# PhaseShiftNetwork.net
KiCad netlist of a schematic drawn in Altium Designer
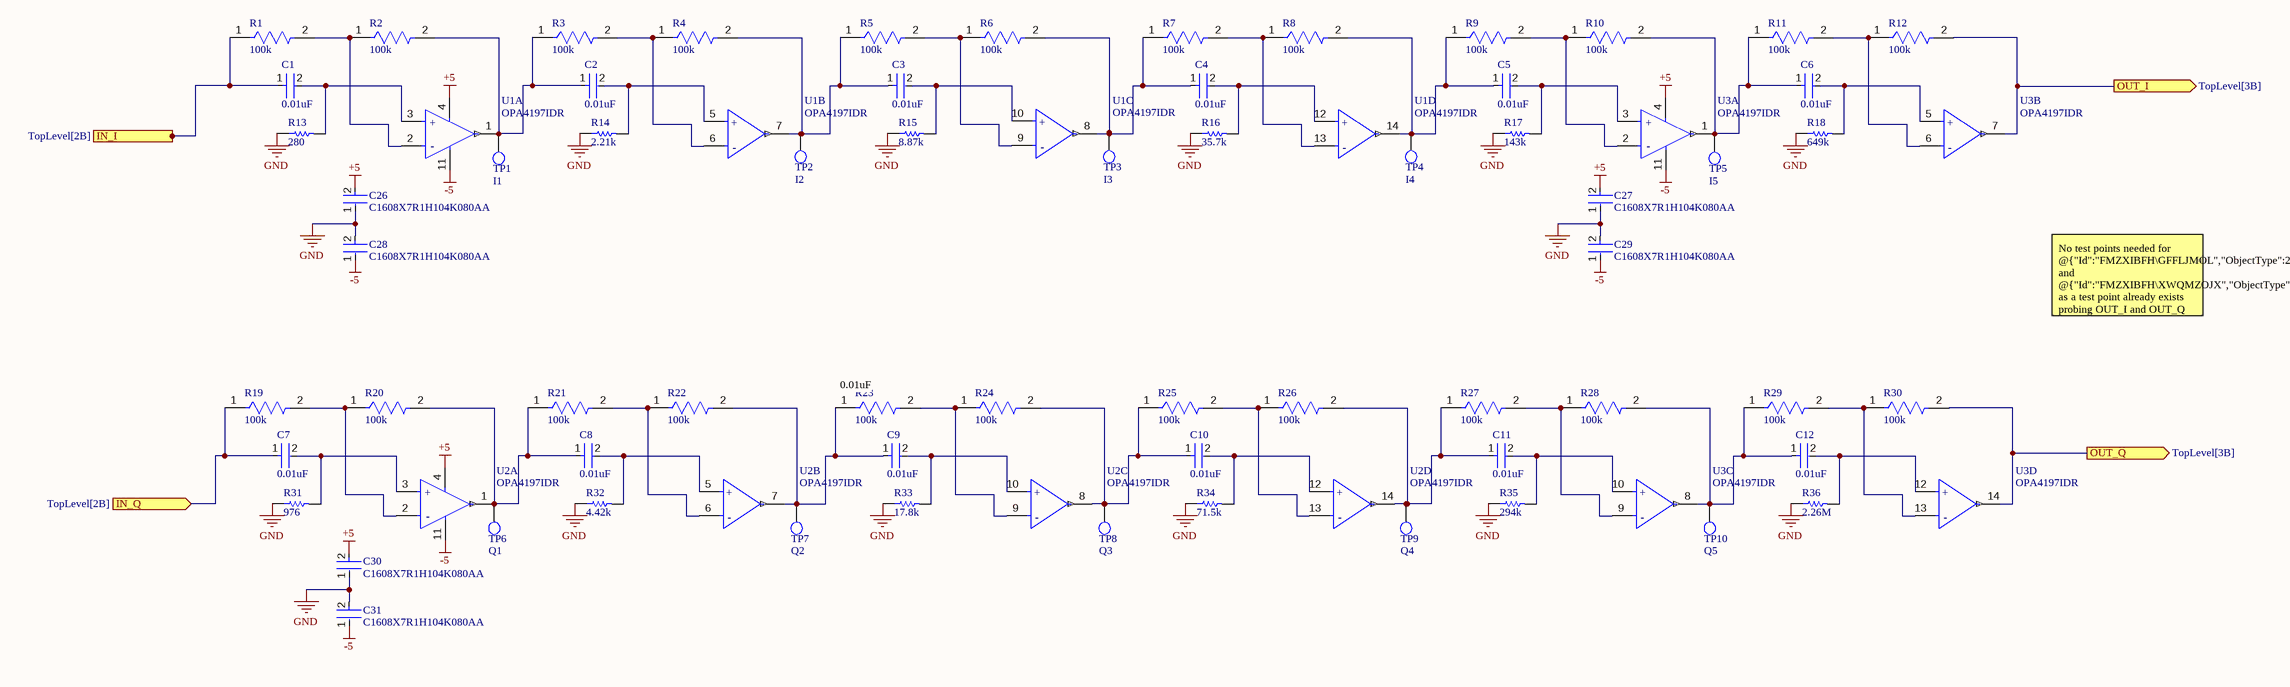
[diagram p0: PhaseShiftNetwork.SchDoc]

(export (version "E")
  (design (tool "Eeschema 10.0.6"))
  (components
    (comp (ref "C1")
      (value "0.01uF")
      (footprint "FP-C0603C-CF-MFG")
      (description "CAP CER 10000PF 25V 1% NP0 0603")
      (fields
        (field (name "MANUFACTURER") "KEMET")
        (field (name "OCTOPART") "https://octopart.com/c0603c103f3gactu-kemet-12577573")
      )
      (libsource (lib "Altium Content Vault") (part "b4654b650e69147ec39a6b967a45e02"))
    )
    (comp (ref "C2")
      (value "0.01uF")
      (footprint "FP-C0603C-CF-MFG")
      (description "CAP CER 10000PF 25V 1% NP0 0603")
      (fields
        (field (name "MANUFACTURER") "KEMET")
        (field (name "OCTOPART") "https://octopart.com/c0603c103f3gactu-kemet-12577573")
      )
      (libsource (lib "Altium Content Vault") (part "b4654b650e69147ec39a6b967a45e02"))
    )
    (comp (ref "C3")
      (value "0.01uF")
      (footprint "FP-C0603C-CF-MFG")
      (description "CAP CER 10000PF 25V 1% NP0 0603")
      (fields
        (field (name "MANUFACTURER") "KEMET")
        (field (name "OCTOPART") "https://octopart.com/c0603c103f3gactu-kemet-12577573")
      )
      (libsource (lib "Altium Content Vault") (part "b4654b650e69147ec39a6b967a45e02"))
    )
    (comp (ref "C4")
      (value "0.01uF")
      (footprint "FP-C0603C-CF-MFG")
      (description "CAP CER 10000PF 25V 1% NP0 0603")
      (fields
        (field (name "MANUFACTURER") "KEMET")
        (field (name "OCTOPART") "https://octopart.com/c0603c103f3gactu-kemet-12577573")
      )
      (libsource (lib "Altium Content Vault") (part "b4654b650e69147ec39a6b967a45e02"))
    )
    (comp (ref "C5")
      (value "0.01uF")
      (footprint "FP-C0603C-CF-MFG")
      (description "CAP CER 10000PF 25V 1% NP0 0603")
      (fields
        (field (name "MANUFACTURER") "KEMET")
        (field (name "OCTOPART") "https://octopart.com/c0603c103f3gactu-kemet-12577573")
      )
      (libsource (lib "Altium Content Vault") (part "b4654b650e69147ec39a6b967a45e02"))
    )
    (comp (ref "C6")
      (value "0.01uF")
      (footprint "FP-C0603C-CF-MFG")
      (description "CAP CER 10000PF 25V 1% NP0 0603")
      (fields
        (field (name "MANUFACTURER") "KEMET")
        (field (name "OCTOPART") "https://octopart.com/c0603c103f3gactu-kemet-12577573")
      )
      (libsource (lib "Altium Content Vault") (part "b4654b650e69147ec39a6b967a45e02"))
    )
    (comp (ref "C7")
      (value "0.01uF")
      (footprint "FP-C0603C-CF-MFG")
      (description "CAP CER 10000PF 25V 1% NP0 0603")
      (fields
        (field (name "MANUFACTURER") "KEMET")
        (field (name "OCTOPART") "https://octopart.com/c0603c103f3gactu-kemet-12577573")
      )
      (libsource (lib "Altium Content Vault") (part "b4654b650e69147ec39a6b967a45e02"))
    )
    (comp (ref "C8")
      (value "0.01uF")
      (footprint "FP-C0603C-CF-MFG")
      (description "CAP CER 10000PF 25V 1% NP0 0603")
      (fields
        (field (name "MANUFACTURER") "KEMET")
        (field (name "OCTOPART") "https://octopart.com/c0603c103f3gactu-kemet-12577573")
      )
      (libsource (lib "Altium Content Vault") (part "b4654b650e69147ec39a6b967a45e02"))
    )
    (comp (ref "C9")
      (value "0.01uF")
      (footprint "FP-C0603C-CF-MFG")
      (description "CAP CER 10000PF 25V 1% NP0 0603")
      (fields
        (field (name "MANUFACTURER") "KEMET")
        (field (name "OCTOPART") "https://octopart.com/c0603c103f3gactu-kemet-12577573")
      )
      (libsource (lib "Altium Content Vault") (part "b4654b650e69147ec39a6b967a45e02"))
    )
    (comp (ref "C10")
      (value "0.01uF")
      (footprint "FP-C0603C-CF-MFG")
      (description "CAP CER 10000PF 25V 1% NP0 0603")
      (fields
        (field (name "MANUFACTURER") "KEMET")
        (field (name "OCTOPART") "https://octopart.com/c0603c103f3gactu-kemet-12577573")
      )
      (libsource (lib "Altium Content Vault") (part "b4654b650e69147ec39a6b967a45e02"))
    )
    (comp (ref "C11")
      (value "0.01uF")
      (footprint "FP-C0603C-CF-MFG")
      (description "CAP CER 10000PF 25V 1% NP0 0603")
      (fields
        (field (name "MANUFACTURER") "KEMET")
        (field (name "OCTOPART") "https://octopart.com/c0603c103f3gactu-kemet-12577573")
      )
      (libsource (lib "Altium Content Vault") (part "b4654b650e69147ec39a6b967a45e02"))
    )
    (comp (ref "C12")
      (value "0.01uF")
      (footprint "FP-C0603C-CF-MFG")
      (description "CAP CER 10000PF 25V 1% NP0 0603")
      (fields
        (field (name "MANUFACTURER") "KEMET")
        (field (name "OCTOPART") "https://octopart.com/c0603c103f3gactu-kemet-12577573")
      )
      (libsource (lib "Altium Content Vault") (part "b4654b650e69147ec39a6b967a45e02"))
    )
    (comp (ref "C26")
      (value "C1608X7R1H104K080AA")
      (footprint "FP-C1608-080-0_1-MFG")
      (description "Multilayer Ceramic Capacitors 100nF ±10% 50V X7R SMD 0603")
      (fields (field (name "VOLTAGE") "50V") (field (name "TOLERANCE") "10%"))
      (libsource (lib "Altium Content Vault") (part "236180d848d6139a670b325ea6854c9"))
    )
    (comp (ref "C27")
      (value "C1608X7R1H104K080AA")
      (footprint "FP-C1608-080-0_1-MFG")
      (description "Multilayer Ceramic Capacitors 100nF ±10% 50V X7R SMD 0603")
      (fields (field (name "VOLTAGE") "50V") (field (name "TOLERANCE") "10%"))
      (libsource (lib "Altium Content Vault") (part "236180d848d6139a670b325ea6854c9"))
    )
    (comp (ref "C28")
      (value "C1608X7R1H104K080AA")
      (footprint "FP-C1608-080-0_1-MFG")
      (description "Multilayer Ceramic Capacitors 100nF ±10% 50V X7R SMD 0603")
      (fields (field (name "VOLTAGE") "50V") (field (name "TOLERANCE") "10%"))
      (libsource (lib "Altium Content Vault") (part "236180d848d6139a670b325ea6854c9"))
    )
    (comp (ref "C29")
      (value "C1608X7R1H104K080AA")
      (footprint "FP-C1608-080-0_1-MFG")
      (description "Multilayer Ceramic Capacitors 100nF ±10% 50V X7R SMD 0603")
      (fields (field (name "VOLTAGE") "50V") (field (name "TOLERANCE") "10%"))
      (libsource (lib "Altium Content Vault") (part "236180d848d6139a670b325ea6854c9"))
    )
    (comp (ref "C30")
      (value "C1608X7R1H104K080AA")
      (footprint "FP-C1608-080-0_1-MFG")
      (description "Multilayer Ceramic Capacitors 100nF ±10% 50V X7R SMD 0603")
      (fields (field (name "VOLTAGE") "50V") (field (name "TOLERANCE") "10%"))
      (libsource (lib "Altium Content Vault") (part "236180d848d6139a670b325ea6854c9"))
    )
    (comp (ref "C31")
      (value "C1608X7R1H104K080AA")
      (footprint "FP-C1608-080-0_1-MFG")
      (description "Multilayer Ceramic Capacitors 100nF ±10% 50V X7R SMD 0603")
      (fields (field (name "VOLTAGE") "50V") (field (name "TOLERANCE") "10%"))
      (libsource (lib "Altium Content Vault") (part "236180d848d6139a670b325ea6854c9"))
    )
    (comp (ref "R1")
      (value "100k")
      (footprint "FP-RC0805-0_6-IPC_C")
      (description "RES 100K OHM 1% 1/8W 0805")
      (fields (field (name "TOLERANCE") "1%"))
      (libsource (lib "Altium Content Vault") (part "1029c3af85768c4190bb7ad29bc67b5"))
    )
    (comp (ref "R2")
      (value "100k")
      (footprint "FP-RC0805-0_6-IPC_C")
      (description "RES 100K OHM 1% 1/8W 0805")
      (fields (field (name "TOLERANCE") "1%"))
      (libsource (lib "Altium Content Vault") (part "1029c3af85768c4190bb7ad29bc67b5"))
    )
    (comp (ref "R3")
      (value "100k")
      (footprint "FP-RC0805-0_6-IPC_C")
      (description "RES 100K OHM 1% 1/8W 0805")
      (fields (field (name "TOLERANCE") "1%"))
      (libsource (lib "Altium Content Vault") (part "1029c3af85768c4190bb7ad29bc67b5"))
    )
    (comp (ref "R4")
      (value "100k")
      (footprint "FP-RC0805-0_6-IPC_C")
      (description "RES 100K OHM 1% 1/8W 0805")
      (fields (field (name "TOLERANCE") "1%"))
      (libsource (lib "Altium Content Vault") (part "1029c3af85768c4190bb7ad29bc67b5"))
    )
    (comp (ref "R5")
      (value "100k")
      (footprint "FP-RC0805-0_6-IPC_C")
      (description "RES 100K OHM 1% 1/8W 0805")
      (fields (field (name "TOLERANCE") "1%"))
      (libsource (lib "Altium Content Vault") (part "1029c3af85768c4190bb7ad29bc67b5"))
    )
    (comp (ref "R6")
      (value "100k")
      (footprint "FP-RC0805-0_6-IPC_C")
      (description "RES 100K OHM 1% 1/8W 0805")
      (fields (field (name "TOLERANCE") "1%"))
      (libsource (lib "Altium Content Vault") (part "1029c3af85768c4190bb7ad29bc67b5"))
    )
    (comp (ref "R7")
      (value "100k")
      (footprint "FP-RC0805-0_6-IPC_C")
      (description "RES 100K OHM 1% 1/8W 0805")
      (fields (field (name "TOLERANCE") "1%"))
      (libsource (lib "Altium Content Vault") (part "1029c3af85768c4190bb7ad29bc67b5"))
    )
    (comp (ref "R8")
      (value "100k")
      (footprint "FP-RC0805-0_6-IPC_C")
      (description "RES 100K OHM 1% 1/8W 0805")
      (fields (field (name "TOLERANCE") "1%"))
      (libsource (lib "Altium Content Vault") (part "1029c3af85768c4190bb7ad29bc67b5"))
    )
    (comp (ref "R9")
      (value "100k")
      (footprint "FP-RC0805-0_6-IPC_C")
      (description "RES 100K OHM 1% 1/8W 0805")
      (fields (field (name "TOLERANCE") "1%"))
      (libsource (lib "Altium Content Vault") (part "1029c3af85768c4190bb7ad29bc67b5"))
    )
    (comp (ref "R10")
      (value "100k")
      (footprint "FP-RC0805-0_6-IPC_C")
      (description "RES 100K OHM 1% 1/8W 0805")
      (fields (field (name "TOLERANCE") "1%"))
      (libsource (lib "Altium Content Vault") (part "1029c3af85768c4190bb7ad29bc67b5"))
    )
    (comp (ref "R11")
      (value "100k")
      (footprint "FP-RC0805-0_6-IPC_C")
      (description "RES 100K OHM 1% 1/8W 0805")
      (fields (field (name "TOLERANCE") "1%"))
      (libsource (lib "Altium Content Vault") (part "1029c3af85768c4190bb7ad29bc67b5"))
    )
    (comp (ref "R12")
      (value "100k")
      (footprint "FP-RC0805-0_6-IPC_C")
      (description "RES 100K OHM 1% 1/8W 0805")
      (fields (field (name "TOLERANCE") "1%"))
      (libsource (lib "Altium Content Vault") (part "1029c3af85768c4190bb7ad29bc67b5"))
    )
    (comp (ref "R13")
      (value "280")
      (footprint "RESC2013X60X35ML10T20")
      (fields (field (name "MANUFACTURER") "Yageo") (field (name "PART NUMBER") "RC0805FR-07280RL"))
      (libsource (lib "Altium Content Vault") (part "RES"))
    )
    (comp (ref "R14")
      (value "2.21k")
      (footprint "RESC2013X60X35ML10T20")
      (fields (field (name "MANUFACTURER") "Yageo") (field (name "PART NUMBER") "RC0805FR-072K21L"))
      (libsource (lib "Altium Content Vault") (part "RES"))
    )
    (comp (ref "R15")
      (value "8.87k")
      (footprint "RESC2013X60X35ML10T20")
      (fields (field (name "MANUFACTURER") "Yageo") (field (name "PART NUMBER") "RC0805FR-07280RL"))
      (libsource (lib "Altium Content Vault") (part "RES"))
    )
    (comp (ref "R16")
      (value "35.7k")
      (footprint "RESC2013X60X35ML10T20")
      (fields (field (name "MANUFACTURER") "Yageo") (field (name "PART NUMBER") "RC0805FR-07280RL"))
      (libsource (lib "Altium Content Vault") (part "RES"))
    )
    (comp (ref "R17")
      (value "143k")
      (footprint "RESC2013X60X35ML10T20")
      (fields (field (name "MANUFACTURER") "Yageo") (field (name "PART NUMBER") "RC0805FR-07280RL"))
      (libsource (lib "Altium Content Vault") (part "RES"))
    )
    (comp (ref "R18")
      (value "649k")
      (footprint "RESC2013X60X35ML10T20")
      (fields (field (name "MANUFACTURER") "Yageo") (field (name "PART NUMBER") "RC0805FR-07280RL"))
      (libsource (lib "Altium Content Vault") (part "RES"))
    )
    (comp (ref "R19")
      (value "100k")
      (footprint "FP-RC0805-0_6-IPC_C")
      (description "RES 100K OHM 1% 1/8W 0805")
      (fields (field (name "TOLERANCE") "1%"))
      (libsource (lib "Altium Content Vault") (part "1029c3af85768c4190bb7ad29bc67b5"))
    )
    (comp (ref "R20")
      (value "100k")
      (footprint "FP-RC0805-0_6-IPC_C")
      (description "RES 100K OHM 1% 1/8W 0805")
      (fields (field (name "TOLERANCE") "1%"))
      (libsource (lib "Altium Content Vault") (part "1029c3af85768c4190bb7ad29bc67b5"))
    )
    (comp (ref "R21")
      (value "100k")
      (footprint "FP-RC0805-0_6-IPC_C")
      (description "RES 100K OHM 1% 1/8W 0805")
      (fields (field (name "TOLERANCE") "1%"))
      (libsource (lib "Altium Content Vault") (part "1029c3af85768c4190bb7ad29bc67b5"))
    )
    (comp (ref "R22")
      (value "100k")
      (footprint "FP-RC0805-0_6-IPC_C")
      (description "RES 100K OHM 1% 1/8W 0805")
      (fields (field (name "TOLERANCE") "1%"))
      (libsource (lib "Altium Content Vault") (part "1029c3af85768c4190bb7ad29bc67b5"))
    )
    (comp (ref "R23")
      (value "100k")
      (footprint "FP-RC0805-0_6-IPC_C")
      (description "RES 100K OHM 1% 1/8W 0805")
      (fields (field (name "TOLERANCE") "1%"))
      (libsource (lib "Altium Content Vault") (part "1029c3af85768c4190bb7ad29bc67b5"))
    )
    (comp (ref "R24")
      (value "100k")
      (footprint "FP-RC0805-0_6-IPC_C")
      (description "RES 100K OHM 1% 1/8W 0805")
      (fields (field (name "TOLERANCE") "1%"))
      (libsource (lib "Altium Content Vault") (part "1029c3af85768c4190bb7ad29bc67b5"))
    )
    (comp (ref "R25")
      (value "100k")
      (footprint "FP-RC0805-0_6-IPC_C")
      (description "RES 100K OHM 1% 1/8W 0805")
      (fields (field (name "TOLERANCE") "1%"))
      (libsource (lib "Altium Content Vault") (part "1029c3af85768c4190bb7ad29bc67b5"))
    )
    (comp (ref "R26")
      (value "100k")
      (footprint "FP-RC0805-0_6-IPC_C")
      (description "RES 100K OHM 1% 1/8W 0805")
      (fields (field (name "TOLERANCE") "1%"))
      (libsource (lib "Altium Content Vault") (part "1029c3af85768c4190bb7ad29bc67b5"))
    )
    (comp (ref "R27")
      (value "100k")
      (footprint "FP-RC0805-0_6-IPC_C")
      (description "RES 100K OHM 1% 1/8W 0805")
      (fields (field (name "TOLERANCE") "1%"))
      (libsource (lib "Altium Content Vault") (part "1029c3af85768c4190bb7ad29bc67b5"))
    )
    (comp (ref "R28")
      (value "100k")
      (footprint "FP-RC0805-0_6-IPC_C")
      (description "RES 100K OHM 1% 1/8W 0805")
      (fields (field (name "TOLERANCE") "1%"))
      (libsource (lib "Altium Content Vault") (part "1029c3af85768c4190bb7ad29bc67b5"))
    )
    (comp (ref "R29")
      (value "100k")
      (footprint "FP-RC0805-0_6-IPC_C")
      (description "RES 100K OHM 1% 1/8W 0805")
      (fields (field (name "TOLERANCE") "1%"))
      (libsource (lib "Altium Content Vault") (part "1029c3af85768c4190bb7ad29bc67b5"))
    )
    (comp (ref "R30")
      (value "100k")
      (footprint "FP-RC0805-0_6-IPC_C")
      (description "RES 100K OHM 1% 1/8W 0805")
      (fields (field (name "TOLERANCE") "1%"))
      (libsource (lib "Altium Content Vault") (part "1029c3af85768c4190bb7ad29bc67b5"))
    )
    (comp (ref "R31")
      (value "976")
      (footprint "RESC2013X60X35ML10T20")
      (fields (field (name "MANUFACTURER") "Yageo") (field (name "PART NUMBER") "RC0805FR-07280RL"))
      (libsource (lib "Altium Content Vault") (part "RES"))
    )
    (comp (ref "R32")
      (value "4.42k")
      (footprint "RESC2013X60X35ML10T20")
      (fields (field (name "MANUFACTURER") "Yageo") (field (name "PART NUMBER") "RC0805FR-07280RL"))
      (libsource (lib "Altium Content Vault") (part "RES"))
    )
    (comp (ref "R33")
      (value "17.8k")
      (footprint "RESC2013X60X35ML10T20")
      (fields (field (name "MANUFACTURER") "Yageo") (field (name "PART NUMBER") "RC0805FR-07280RL"))
      (libsource (lib "Altium Content Vault") (part "RES"))
    )
    (comp (ref "R34")
      (value "71.5k")
      (footprint "RESC2013X60X35ML10T20")
      (fields (field (name "MANUFACTURER") "Yageo") (field (name "PART NUMBER") "RC0805FR-07280RL"))
      (libsource (lib "Altium Content Vault") (part "RES"))
    )
    (comp (ref "R35")
      (value "294k")
      (footprint "RESC2013X60X35ML10T20")
      (fields (field (name "MANUFACTURER") "Yageo") (field (name "PART NUMBER") "RC0805FR-07280RL"))
      (libsource (lib "Altium Content Vault") (part "RES"))
    )
    (comp (ref "R36")
      (value "2.26M")
      (footprint "RESC2013X60X35ML10T20")
      (fields (field (name "MANUFACTURER") "Yageo") (field (name "PART NUMBER") "RC0805FR-07280RL"))
      (libsource (lib "Altium Content Vault") (part "RES"))
    )
    (comp (ref "TP1") (value "I1") (footprint "TP-PAD") (libsource (lib "TestPoints") (part "TP-PAD")))
    (comp (ref "TP2") (value "I2") (footprint "TP-PAD") (libsource (lib "TestPoints") (part "TP-PAD")))
    (comp (ref "TP3") (value "I3") (footprint "TP-PAD") (libsource (lib "TestPoints") (part "TP-PAD")))
    (comp (ref "TP4") (value "I4") (footprint "TP-PAD") (libsource (lib "TestPoints") (part "TP-PAD")))
    (comp (ref "TP5") (value "I5") (footprint "TP-PAD") (libsource (lib "TestPoints") (part "TP-PAD")))
    (comp (ref "TP6") (value "Q1") (footprint "TP-PAD") (libsource (lib "TestPoints") (part "TP-PAD")))
    (comp (ref "TP7") (value "Q2") (footprint "TP-PAD") (libsource (lib "TestPoints") (part "TP-PAD")))
    (comp (ref "TP8") (value "Q3") (footprint "TP-PAD") (libsource (lib "TestPoints") (part "TP-PAD")))
    (comp (ref "TP9") (value "Q4") (footprint "TP-PAD") (libsource (lib "TestPoints") (part "TP-PAD")))
    (comp (ref "TP10") (value "Q5") (footprint "TP-PAD") (libsource (lib "TestPoints") (part "TP-PAD")))
    (comp (ref "U1")
      (value "OPA4197IDR")
      (footprint "FP-D0014A-MFG")
      (description "IC OPAMP GP 4 CIRCUIT 14SOIC")
      (libsource (lib "Altium Content Vault") (part "684fa0f315d4229452f837ea2b10642"))
    )
    (comp (ref "U2")
      (value "OPA4197IDR")
      (footprint "FP-D0014A-MFG")
      (description "IC OPAMP GP 4 CIRCUIT 14SOIC")
      (libsource (lib "Altium Content Vault") (part "684fa0f315d4229452f837ea2b10642"))
    )
    (comp (ref "U3")
      (value "OPA4197IDR")
      (footprint "FP-D0014A-MFG")
      (description "IC OPAMP GP 4 CIRCUIT 14SOIC")
      (libsource (lib "Altium Content Vault") (part "684fa0f315d4229452f837ea2b10642"))
    )
  )
  (nets
    (net (code "1") (name "+5") (class "Default")
      (node (ref "C26") (pin "2") (pinfunction "2_2") (pintype "passive"))
      (node (ref "C27") (pin "2") (pinfunction "2_2") (pintype "passive"))
      (node (ref "C30") (pin "2") (pinfunction "2_2") (pintype "passive"))
      (node (ref "U1") (pin "4") (pinfunction "V+_4") (pintype "power_in"))
      (node (ref "U2") (pin "4") (pinfunction "V+_4") (pintype "power_in"))
      (node (ref "U3") (pin "4") (pinfunction "V+_4") (pintype "power_in"))
    )
    (net (code "2") (name "-5") (class "Default")
      (node (ref "C28") (pin "1") (pinfunction "1_1") (pintype "passive"))
      (node (ref "C29") (pin "1") (pinfunction "1_1") (pintype "passive"))
      (node (ref "C31") (pin "1") (pinfunction "1_1") (pintype "passive"))
      (node (ref "U1") (pin "11") (pinfunction "V-_11") (pintype "power_in"))
      (node (ref "U2") (pin "11") (pinfunction "V-_11") (pintype "power_in"))
      (node (ref "U3") (pin "11") (pinfunction "V-_11") (pintype "power_in"))
    )
    (net (code "3") (name "/IN_I") (class "Default")
      (node (ref "C1") (pin "1") (pinfunction "1_1") (pintype "passive"))
      (node (ref "R1") (pin "1") (pinfunction "1_1") (pintype "passive"))
    )
    (net (code "4") (name "/IN_Q") (class "Default")
      (node (ref "C7") (pin "1") (pinfunction "1_1") (pintype "passive"))
      (node (ref "R19") (pin "1") (pinfunction "1_1") (pintype "passive"))
    )
    (net (code "5") (name "/OUT_I") (class "Default")
      (node (ref "R12") (pin "2") (pinfunction "2_2") (pintype "passive"))
      (node (ref "U3") (pin "7") (pinfunction "OUT_B_7") (pintype "output"))
    )
    (net (code "6") (name "/OUT_Q") (class "Default")
      (node (ref "R30") (pin "2") (pinfunction "2_2") (pintype "passive"))
      (node (ref "U3") (pin "14") (pinfunction "OUT_D_14") (pintype "output"))
    )
    (net (code "7") (name "GND") (class "Default")
      (node (ref "C26") (pin "1") (pinfunction "1_1") (pintype "passive"))
      (node (ref "C27") (pin "1") (pinfunction "1_1") (pintype "passive"))
      (node (ref "C28") (pin "2") (pinfunction "2_2") (pintype "passive"))
      (node (ref "C29") (pin "2") (pinfunction "2_2") (pintype "passive"))
      (node (ref "C30") (pin "1") (pinfunction "1_1") (pintype "passive"))
      (node (ref "C31") (pin "2") (pinfunction "2_2") (pintype "passive"))
      (node (ref "R13") (pin "1") (pinfunction "1_1") (pintype "passive"))
      (node (ref "R14") (pin "1") (pinfunction "1_1") (pintype "passive"))
      (node (ref "R15") (pin "1") (pinfunction "1_1") (pintype "passive"))
      (node (ref "R16") (pin "1") (pinfunction "1_1") (pintype "passive"))
      (node (ref "R17") (pin "1") (pinfunction "1_1") (pintype "passive"))
      (node (ref "R18") (pin "1") (pinfunction "1_1") (pintype "passive"))
      (node (ref "R31") (pin "1") (pinfunction "1_1") (pintype "passive"))
      (node (ref "R32") (pin "1") (pinfunction "1_1") (pintype "passive"))
      (node (ref "R33") (pin "1") (pinfunction "1_1") (pintype "passive"))
      (node (ref "R34") (pin "1") (pinfunction "1_1") (pintype "passive"))
      (node (ref "R35") (pin "1") (pinfunction "1_1") (pintype "passive"))
      (node (ref "R36") (pin "1") (pinfunction "1_1") (pintype "passive"))
    )
    (net (code "8") (name "Net-(U1A-+IN_A)") (class "Default")
      (node (ref "C1") (pin "2") (pinfunction "2_2") (pintype "passive"))
      (node (ref "R13") (pin "2") (pinfunction "2_2") (pintype "passive"))
      (node (ref "U1") (pin "3") (pinfunction "+IN_A_3") (pintype "tri_state"))
    )
    (net (code "9") (name "Net-(U1A--IN_A)") (class "Default")
      (node (ref "R1") (pin "2") (pinfunction "2_2") (pintype "passive"))
      (node (ref "R2") (pin "1") (pinfunction "1_1") (pintype "passive"))
      (node (ref "U1") (pin "2") (pinfunction "-IN_A_2") (pintype "tri_state"))
    )
    (net (code "10") (name "Net-(U1A-OUT_A)") (class "Default")
      (node (ref "C2") (pin "1") (pinfunction "1_1") (pintype "passive"))
      (node (ref "R2") (pin "2") (pinfunction "2_2") (pintype "passive"))
      (node (ref "R3") (pin "1") (pinfunction "1_1") (pintype "passive"))
      (node (ref "TP1") (pin "1") (pinfunction "1_1") (pintype "passive"))
      (node (ref "U1") (pin "1") (pinfunction "OUT_A_1") (pintype "output"))
    )
    (net (code "11") (name "Net-(U1B-+IN_B)") (class "Default")
      (node (ref "C2") (pin "2") (pinfunction "2_2") (pintype "passive"))
      (node (ref "R14") (pin "2") (pinfunction "2_2") (pintype "passive"))
      (node (ref "U1") (pin "5") (pinfunction "+IN_B_5") (pintype "tri_state"))
    )
    (net (code "12") (name "Net-(U1B--IN_B)") (class "Default")
      (node (ref "R3") (pin "2") (pinfunction "2_2") (pintype "passive"))
      (node (ref "R4") (pin "1") (pinfunction "1_1") (pintype "passive"))
      (node (ref "U1") (pin "6") (pinfunction "-IN_B_6") (pintype "tri_state"))
    )
    (net (code "13") (name "Net-(U1B-OUT_B)") (class "Default")
      (node (ref "C3") (pin "1") (pinfunction "1_1") (pintype "passive"))
      (node (ref "R4") (pin "2") (pinfunction "2_2") (pintype "passive"))
      (node (ref "R5") (pin "1") (pinfunction "1_1") (pintype "passive"))
      (node (ref "TP2") (pin "1") (pinfunction "1_1") (pintype "passive"))
      (node (ref "U1") (pin "7") (pinfunction "OUT_B_7") (pintype "output"))
    )
    (net (code "14") (name "Net-(U1C-+IN_C)") (class "Default")
      (node (ref "C3") (pin "2") (pinfunction "2_2") (pintype "passive"))
      (node (ref "R15") (pin "2") (pinfunction "2_2") (pintype "passive"))
      (node (ref "U1") (pin "10") (pinfunction "+IN_C_10") (pintype "tri_state"))
    )
    (net (code "15") (name "Net-(U1C--IN_C)") (class "Default")
      (node (ref "R5") (pin "2") (pinfunction "2_2") (pintype "passive"))
      (node (ref "R6") (pin "1") (pinfunction "1_1") (pintype "passive"))
      (node (ref "U1") (pin "9") (pinfunction "-IN_C_9") (pintype "tri_state"))
    )
    (net (code "16") (name "Net-(U1C-OUT_C)") (class "Default")
      (node (ref "C4") (pin "1") (pinfunction "1_1") (pintype "passive"))
      (node (ref "R6") (pin "2") (pinfunction "2_2") (pintype "passive"))
      (node (ref "R7") (pin "1") (pinfunction "1_1") (pintype "passive"))
      (node (ref "TP3") (pin "1") (pinfunction "1_1") (pintype "passive"))
      (node (ref "U1") (pin "8") (pinfunction "OUT_C_8") (pintype "output"))
    )
    (net (code "17") (name "Net-(U1D-+IN_D)") (class "Default")
      (node (ref "C4") (pin "2") (pinfunction "2_2") (pintype "passive"))
      (node (ref "R16") (pin "2") (pinfunction "2_2") (pintype "passive"))
      (node (ref "U1") (pin "12") (pinfunction "+IN_D_12") (pintype "tri_state"))
    )
    (net (code "18") (name "Net-(U1D--IN_D)") (class "Default")
      (node (ref "R7") (pin "2") (pinfunction "2_2") (pintype "passive"))
      (node (ref "R8") (pin "1") (pinfunction "1_1") (pintype "passive"))
      (node (ref "U1") (pin "13") (pinfunction "-IN_D_13") (pintype "tri_state"))
    )
    (net (code "19") (name "Net-(U1D-OUT_D)") (class "Default")
      (node (ref "C5") (pin "1") (pinfunction "1_1") (pintype "passive"))
      (node (ref "R8") (pin "2") (pinfunction "2_2") (pintype "passive"))
      (node (ref "R9") (pin "1") (pinfunction "1_1") (pintype "passive"))
      (node (ref "TP4") (pin "1") (pinfunction "1_1") (pintype "passive"))
      (node (ref "U1") (pin "14") (pinfunction "OUT_D_14") (pintype "output"))
    )
    (net (code "20") (name "Net-(U2A-+IN_A)") (class "Default")
      (node (ref "C7") (pin "2") (pinfunction "2_2") (pintype "passive"))
      (node (ref "R31") (pin "2") (pinfunction "2_2") (pintype "passive"))
      (node (ref "U2") (pin "3") (pinfunction "+IN_A_3") (pintype "tri_state"))
    )
    (net (code "21") (name "Net-(U2A--IN_A)") (class "Default")
      (node (ref "R19") (pin "2") (pinfunction "2_2") (pintype "passive"))
      (node (ref "R20") (pin "1") (pinfunction "1_1") (pintype "passive"))
      (node (ref "U2") (pin "2") (pinfunction "-IN_A_2") (pintype "tri_state"))
    )
    (net (code "22") (name "Net-(U2A-OUT_A)") (class "Default")
      (node (ref "C8") (pin "1") (pinfunction "1_1") (pintype "passive"))
      (node (ref "R20") (pin "2") (pinfunction "2_2") (pintype "passive"))
      (node (ref "R21") (pin "1") (pinfunction "1_1") (pintype "passive"))
      (node (ref "TP6") (pin "1") (pinfunction "1_1") (pintype "passive"))
      (node (ref "U2") (pin "1") (pinfunction "OUT_A_1") (pintype "output"))
    )
    (net (code "23") (name "Net-(U2B-+IN_B)") (class "Default")
      (node (ref "C8") (pin "2") (pinfunction "2_2") (pintype "passive"))
      (node (ref "R32") (pin "2") (pinfunction "2_2") (pintype "passive"))
      (node (ref "U2") (pin "5") (pinfunction "+IN_B_5") (pintype "tri_state"))
    )
    (net (code "24") (name "Net-(U2B--IN_B)") (class "Default")
      (node (ref "R21") (pin "2") (pinfunction "2_2") (pintype "passive"))
      (node (ref "R22") (pin "1") (pinfunction "1_1") (pintype "passive"))
      (node (ref "U2") (pin "6") (pinfunction "-IN_B_6") (pintype "tri_state"))
    )
    (net (code "25") (name "Net-(U2B-OUT_B)") (class "Default")
      (node (ref "C9") (pin "1") (pinfunction "1_1") (pintype "passive"))
      (node (ref "R22") (pin "2") (pinfunction "2_2") (pintype "passive"))
      (node (ref "R23") (pin "1") (pinfunction "1_1") (pintype "passive"))
      (node (ref "TP7") (pin "1") (pinfunction "1_1") (pintype "passive"))
      (node (ref "U2") (pin "7") (pinfunction "OUT_B_7") (pintype "output"))
    )
    (net (code "26") (name "Net-(U2C-+IN_C)") (class "Default")
      (node (ref "C9") (pin "2") (pinfunction "2_2") (pintype "passive"))
      (node (ref "R33") (pin "2") (pinfunction "2_2") (pintype "passive"))
      (node (ref "U2") (pin "10") (pinfunction "+IN_C_10") (pintype "tri_state"))
    )
    (net (code "27") (name "Net-(U2C--IN_C)") (class "Default")
      (node (ref "R23") (pin "2") (pinfunction "2_2") (pintype "passive"))
      (node (ref "R24") (pin "1") (pinfunction "1_1") (pintype "passive"))
      (node (ref "U2") (pin "9") (pinfunction "-IN_C_9") (pintype "tri_state"))
    )
    (net (code "28") (name "Net-(U2C-OUT_C)") (class "Default")
      (node (ref "C10") (pin "1") (pinfunction "1_1") (pintype "passive"))
      (node (ref "R24") (pin "2") (pinfunction "2_2") (pintype "passive"))
      (node (ref "R25") (pin "1") (pinfunction "1_1") (pintype "passive"))
      (node (ref "TP8") (pin "1") (pinfunction "1_1") (pintype "passive"))
      (node (ref "U2") (pin "8") (pinfunction "OUT_C_8") (pintype "output"))
    )
    (net (code "29") (name "Net-(U2D-+IN_D)") (class "Default")
      (node (ref "C10") (pin "2") (pinfunction "2_2") (pintype "passive"))
      (node (ref "R34") (pin "2") (pinfunction "2_2") (pintype "passive"))
      (node (ref "U2") (pin "12") (pinfunction "+IN_D_12") (pintype "tri_state"))
    )
    (net (code "30") (name "Net-(U2D--IN_D)") (class "Default")
      (node (ref "R25") (pin "2") (pinfunction "2_2") (pintype "passive"))
      (node (ref "R26") (pin "1") (pinfunction "1_1") (pintype "passive"))
      (node (ref "U2") (pin "13") (pinfunction "-IN_D_13") (pintype "tri_state"))
    )
    (net (code "31") (name "Net-(U2D-OUT_D)") (class "Default")
      (node (ref "C11") (pin "1") (pinfunction "1_1") (pintype "passive"))
      (node (ref "R26") (pin "2") (pinfunction "2_2") (pintype "passive"))
      (node (ref "R27") (pin "1") (pinfunction "1_1") (pintype "passive"))
      (node (ref "TP9") (pin "1") (pinfunction "1_1") (pintype "passive"))
      (node (ref "U2") (pin "14") (pinfunction "OUT_D_14") (pintype "output"))
    )
    (net (code "32") (name "Net-(U3A-+IN_A)") (class "Default")
      (node (ref "C5") (pin "2") (pinfunction "2_2") (pintype "passive"))
      (node (ref "R17") (pin "2") (pinfunction "2_2") (pintype "passive"))
      (node (ref "U3") (pin "3") (pinfunction "+IN_A_3") (pintype "tri_state"))
    )
    (net (code "33") (name "Net-(U3A--IN_A)") (class "Default")
      (node (ref "R10") (pin "1") (pinfunction "1_1") (pintype "passive"))
      (node (ref "R9") (pin "2") (pinfunction "2_2") (pintype "passive"))
      (node (ref "U3") (pin "2") (pinfunction "-IN_A_2") (pintype "tri_state"))
    )
    (net (code "34") (name "Net-(U3A-OUT_A)") (class "Default")
      (node (ref "C6") (pin "1") (pinfunction "1_1") (pintype "passive"))
      (node (ref "R10") (pin "2") (pinfunction "2_2") (pintype "passive"))
      (node (ref "R11") (pin "1") (pinfunction "1_1") (pintype "passive"))
      (node (ref "TP5") (pin "1") (pinfunction "1_1") (pintype "passive"))
      (node (ref "U3") (pin "1") (pinfunction "OUT_A_1") (pintype "output"))
    )
    (net (code "35") (name "Net-(U3B-+IN_B)") (class "Default")
      (node (ref "C6") (pin "2") (pinfunction "2_2") (pintype "passive"))
      (node (ref "R18") (pin "2") (pinfunction "2_2") (pintype "passive"))
      (node (ref "U3") (pin "5") (pinfunction "+IN_B_5") (pintype "tri_state"))
    )
    (net (code "36") (name "Net-(U3B--IN_B)") (class "Default")
      (node (ref "R11") (pin "2") (pinfunction "2_2") (pintype "passive"))
      (node (ref "R12") (pin "1") (pinfunction "1_1") (pintype "passive"))
      (node (ref "U3") (pin "6") (pinfunction "-IN_B_6") (pintype "tri_state"))
    )
    (net (code "37") (name "Net-(U3C-+IN_C)") (class "Default")
      (node (ref "C11") (pin "2") (pinfunction "2_2") (pintype "passive"))
      (node (ref "R35") (pin "2") (pinfunction "2_2") (pintype "passive"))
      (node (ref "U3") (pin "10") (pinfunction "+IN_C_10") (pintype "tri_state"))
    )
    (net (code "38") (name "Net-(U3C--IN_C)") (class "Default")
      (node (ref "R27") (pin "2") (pinfunction "2_2") (pintype "passive"))
      (node (ref "R28") (pin "1") (pinfunction "1_1") (pintype "passive"))
      (node (ref "U3") (pin "9") (pinfunction "-IN_C_9") (pintype "tri_state"))
    )
    (net (code "39") (name "Net-(U3C-OUT_C)") (class "Default")
      (node (ref "C12") (pin "1") (pinfunction "1_1") (pintype "passive"))
      (node (ref "R28") (pin "2") (pinfunction "2_2") (pintype "passive"))
      (node (ref "R29") (pin "1") (pinfunction "1_1") (pintype "passive"))
      (node (ref "TP10") (pin "1") (pinfunction "1_1") (pintype "passive"))
      (node (ref "U3") (pin "8") (pinfunction "OUT_C_8") (pintype "output"))
    )
    (net (code "40") (name "Net-(U3D-+IN_D)") (class "Default")
      (node (ref "C12") (pin "2") (pinfunction "2_2") (pintype "passive"))
      (node (ref "R36") (pin "2") (pinfunction "2_2") (pintype "passive"))
      (node (ref "U3") (pin "12") (pinfunction "+IN_D_12") (pintype "tri_state"))
    )
    (net (code "41") (name "Net-(U3D--IN_D)") (class "Default")
      (node (ref "R29") (pin "2") (pinfunction "2_2") (pintype "passive"))
      (node (ref "R30") (pin "1") (pinfunction "1_1") (pintype "passive"))
      (node (ref "U3") (pin "13") (pinfunction "-IN_D_13") (pintype "tri_state"))
    )
  )
)
